# fonte_3v_12v.net
KiCad netlist of a schematic drawn in EAGLE
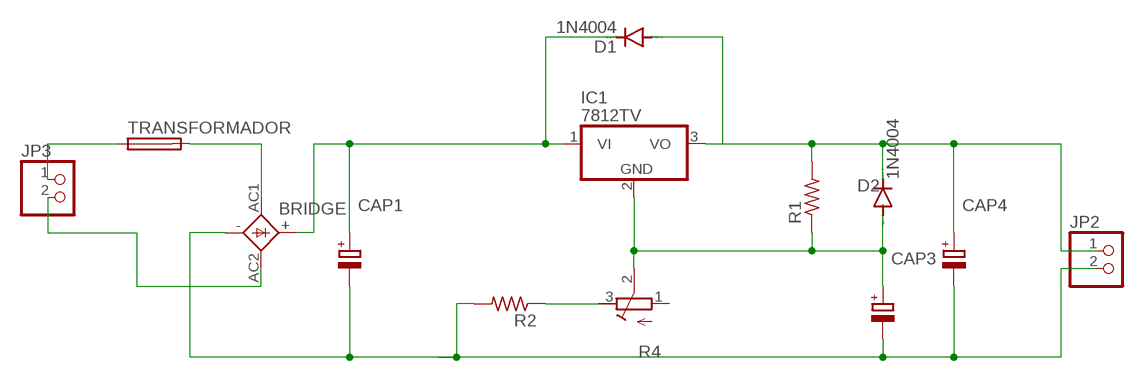
[diagram p0: schematic, sheet 1]

(export (version "E")
  (design (tool "Eeschema 10.0.6"))
  (components
    (comp (ref "BRIDGE")
      (value "2KBB-R")
      (footprint "eagle-import:2KBB-R")
      (libsource (lib "eagle-import") (part "2KBB-R"))
    )
    (comp (ref "CAP1")
      (value "CPOL-EUE5-13")
      (footprint "eagle-import:E5-13")
      (libsource (lib "eagle-import") (part "CPOL-EUE5-13"))
    )
    (comp (ref "CAP3")
      (value "CPOL-EUE5-13")
      (footprint "eagle-import:E5-13")
      (libsource (lib "eagle-import") (part "CPOL-EUE5-13"))
    )
    (comp (ref "CAP4")
      (value "CPOL-EUE5-13")
      (footprint "eagle-import:E5-13")
      (libsource (lib "eagle-import") (part "CPOL-EUE5-13"))
    )
    (comp (ref "D1")
      (value "1N4004")
      (footprint "eagle-import:DO41-10")
      (libsource (lib "eagle-import") (part "1N4004"))
    )
    (comp (ref "D2")
      (value "1N4004")
      (footprint "eagle-import:DO41-10")
      (libsource (lib "eagle-import") (part "1N4004"))
    )
    (comp (ref "IC1")
      (value "7812TV")
      (footprint "eagle-import:TO220V")
      (libsource (lib "eagle-import") (part "78TV12"))
    )
    (comp (ref "JP2")
      (value "PINHD-1X2")
      (footprint "eagle-import:1X02")
      (libsource (lib "eagle-import") (part "PINHD-1X2"))
    )
    (comp (ref "JP3")
      (value "PINHD-1X2")
      (footprint "eagle-import:1X02")
      (libsource (lib "eagle-import") (part "PINHD-1X2"))
    )
    (comp (ref "R1")
      (value "R-US_0204/7")
      (footprint "eagle-import:0204_7")
      (libsource (lib "eagle-import") (part "R-US_0204/7"))
    )
    (comp (ref "R2")
      (value "R-US_0204/7")
      (footprint "eagle-import:0204_7")
      (libsource (lib "eagle-import") (part "R-US_0204/7"))
    )
    (comp (ref "R4")
      (value "R-TRIMM3339P")
      (footprint "eagle-import:RTRIM3339P")
      (libsource (lib "eagle-import") (part "R-TRIMM3339P"))
    )
    (comp (ref "TRANSFORMADOR")
      (value "SH22,5")
      (footprint "eagle-import:SH22,5")
      (fields (field (name "MF") "SCHURTER") (field (name "MPN") "0031.8201"))
      (libsource (lib "eagle-import") (part "SH22,5"))
    )
  )
  (nets
    (net (code "1") (name "Net-(BRIDGE-Pad-)") (class "Default")
      (node (ref "BRIDGE") (pin "-") (pinfunction "-_-") (pintype "passive"))
      (node (ref "CAP1") (pin "-") (pinfunction "-_-") (pintype "passive"))
      (node (ref "CAP3") (pin "-") (pinfunction "-_-") (pintype "passive"))
      (node (ref "CAP4") (pin "-") (pinfunction "-_-") (pintype "passive"))
      (node (ref "JP2") (pin "2") (pinfunction "2_2") (pintype "passive"))
      (node (ref "R2") (pin "2") (pinfunction "2_2") (pintype "passive"))
    )
    (net (code "2") (name "Net-(BRIDGE-PadAC1)") (class "Default")
      (node (ref "BRIDGE") (pin "AC1") (pinfunction "AC1_AC1") (pintype "passive"))
      (node (ref "TRANSFORMADOR") (pin "2") (pinfunction "2_2") (pintype "passive"))
    )
    (net (code "3") (name "Net-(BRIDGE-PadAC2)") (class "Default")
      (node (ref "BRIDGE") (pin "AC2") (pinfunction "AC2_AC2") (pintype "passive"))
      (node (ref "JP3") (pin "2") (pinfunction "2_2") (pintype "passive"))
    )
    (net (code "4") (name "Net-(IC1-GND)") (class "Default")
      (node (ref "CAP3") (pin "+") (pinfunction "+_+") (pintype "passive"))
      (node (ref "D2") (pin "A") (pinfunction "A_A") (pintype "passive"))
      (node (ref "IC1") (pin "2") (pinfunction "GND_2") (pintype "passive"))
      (node (ref "R1") (pin "1") (pinfunction "1_1") (pintype "passive"))
      (node (ref "R4") (pin "2") (pinfunction "S_2") (pintype "passive"))
    )
    (net (code "5") (name "Net-(IC1-VI)") (class "Default")
      (node (ref "BRIDGE") (pin "+") (pinfunction "+_+") (pintype "passive"))
      (node (ref "CAP1") (pin "+") (pinfunction "+_+") (pintype "passive"))
      (node (ref "D1") (pin "C") (pinfunction "C_C") (pintype "passive"))
      (node (ref "IC1") (pin "1") (pinfunction "VI_1") (pintype "input"))
    )
    (net (code "6") (name "Net-(IC1-VO)") (class "Default")
      (node (ref "CAP4") (pin "+") (pinfunction "+_+") (pintype "passive"))
      (node (ref "D1") (pin "A") (pinfunction "A_A") (pintype "passive"))
      (node (ref "D2") (pin "C") (pinfunction "C_C") (pintype "passive"))
      (node (ref "IC1") (pin "3") (pinfunction "VO_3") (pintype "passive"))
      (node (ref "JP2") (pin "1") (pinfunction "1_1") (pintype "passive"))
      (node (ref "R1") (pin "2") (pinfunction "2_2") (pintype "passive"))
    )
    (net (code "7") (name "Net-(JP3-Pad1)") (class "Default")
      (node (ref "JP3") (pin "1") (pinfunction "1_1") (pintype "passive"))
      (node (ref "TRANSFORMADOR") (pin "1") (pinfunction "1_1") (pintype "passive"))
    )
    (net (code "8") (name "Net-(R4-E)") (class "Default")
      (node (ref "R2") (pin "1") (pinfunction "1_1") (pintype "passive"))
      (node (ref "R4") (pin "3") (pinfunction "E_3") (pintype "passive"))
    )
    (net (code "9") (name "unconnected-(R4-A-Pad1)") (class "Default")
      (node (ref "R4") (pin "1") (pinfunction "A_1") (pintype "passive"))
    )
  )
)
